# v2_guc_dag_t_m_savasan.net
KiCad netlist of a schematic drawn in EAGLE
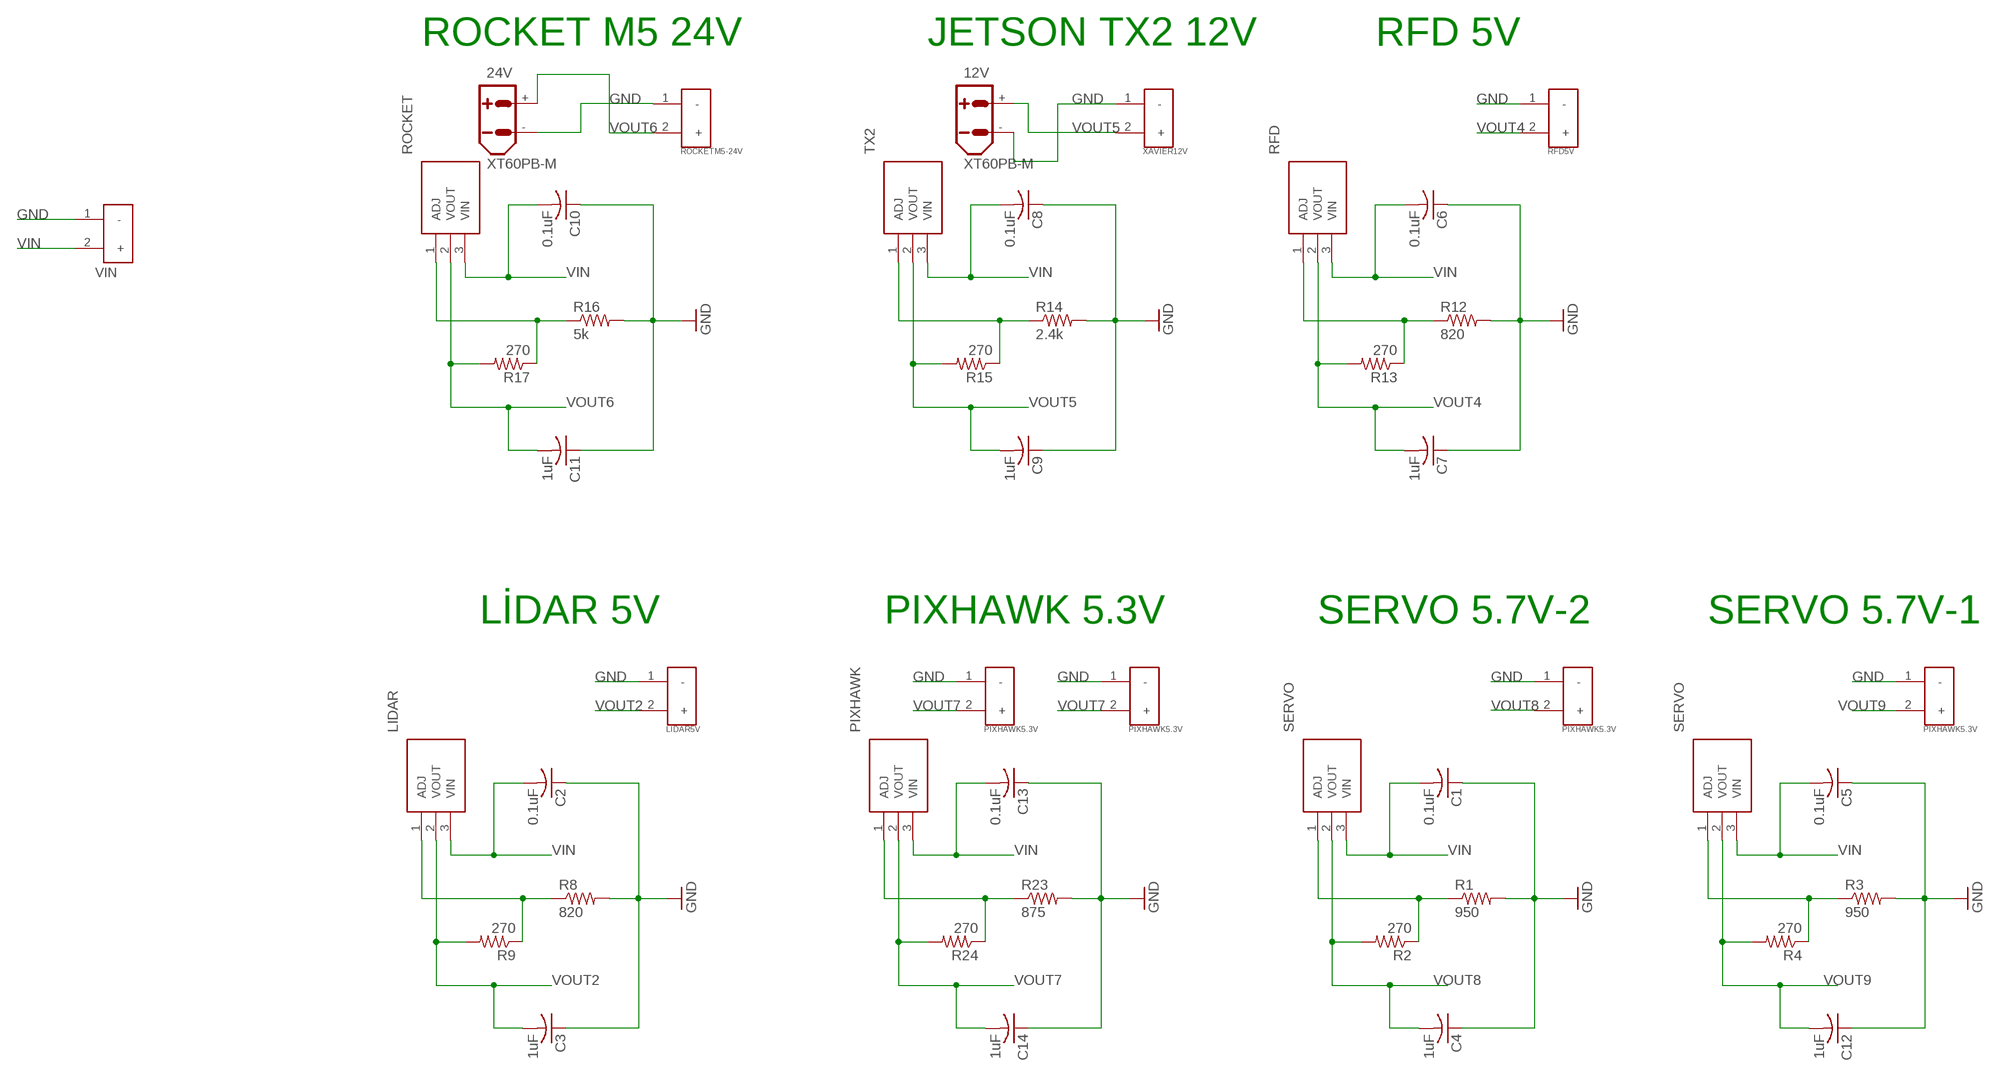
[diagram p0: schematic, sheet 1]

(export (version "E")
  (design (tool "Eeschema 10.0.6"))
  (components
    (comp (ref "12V")
      (value "XT60PB-M")
      (footprint "eagle-import:XT60PB-M")
      (libsource (lib "eagle-import") (part "XT60PB-M"))
    )
    (comp (ref "24V")
      (value "XT60PB-M")
      (footprint "eagle-import:XT60PB-M")
      (libsource (lib "eagle-import") (part "XT60PB-M"))
    )
    (comp (ref "C1")
      (value "0.1uF")
      (footprint "eagle-import:C0402K")
      (libsource (lib "eagle-import") (part "C-USC0402K"))
    )
    (comp (ref "C2")
      (value "0.1uF")
      (footprint "eagle-import:C0402K")
      (libsource (lib "eagle-import") (part "C-USC0402K"))
    )
    (comp (ref "C3")
      (value "1uF")
      (footprint "eagle-import:C0402K")
      (libsource (lib "eagle-import") (part "C-USC0402K"))
    )
    (comp (ref "C4")
      (value "1uF")
      (footprint "eagle-import:C0402K")
      (libsource (lib "eagle-import") (part "C-USC0402K"))
    )
    (comp (ref "C5")
      (value "0.1uF")
      (footprint "eagle-import:C0402K")
      (libsource (lib "eagle-import") (part "C-USC0402K"))
    )
    (comp (ref "C6")
      (value "0.1uF")
      (footprint "eagle-import:C0402K")
      (libsource (lib "eagle-import") (part "C-USC0402K"))
    )
    (comp (ref "C7")
      (value "1uF")
      (footprint "eagle-import:C0402K")
      (libsource (lib "eagle-import") (part "C-USC0402K"))
    )
    (comp (ref "C8")
      (value "0.1uF")
      (footprint "eagle-import:C0402K")
      (libsource (lib "eagle-import") (part "C-USC0402K"))
    )
    (comp (ref "C9")
      (value "1uF")
      (footprint "eagle-import:C0402K")
      (libsource (lib "eagle-import") (part "C-USC0402K"))
    )
    (comp (ref "C10")
      (value "0.1uF")
      (footprint "eagle-import:C0402K")
      (libsource (lib "eagle-import") (part "C-USC0402K"))
    )
    (comp (ref "C11")
      (value "1uF")
      (footprint "eagle-import:C0402K")
      (libsource (lib "eagle-import") (part "C-USC0402K"))
    )
    (comp (ref "C12")
      (value "1uF")
      (footprint "eagle-import:C0402K")
      (libsource (lib "eagle-import") (part "C-USC0402K"))
    )
    (comp (ref "C13")
      (value "0.1uF")
      (footprint "eagle-import:C0402K")
      (libsource (lib "eagle-import") (part "C-USC0402K"))
    )
    (comp (ref "C14")
      (value "1uF")
      (footprint "eagle-import:C0402K")
      (libsource (lib "eagle-import") (part "C-USC0402K"))
    )
    (comp (ref "IC5")
      (value "LIDAR")
      (footprint "eagle-import:TO254P470X1028X1955-3P")
      (fields
        (field (name "ARROW_PART_NUMBER") "LM338T/NOPB")
        (field (name "MOUSER_PART_NUMBER") "926-LM338T/NOPB")
      )
      (libsource (lib "eagle-import") (part "LM338T_NOPB"))
    )
    (comp (ref "IC7")
      (value "RFD")
      (footprint "eagle-import:TO254P470X1028X1955-3P")
      (fields
        (field (name "ARROW_PART_NUMBER") "LM338T/NOPB")
        (field (name "MOUSER_PART_NUMBER") "926-LM338T/NOPB")
      )
      (libsource (lib "eagle-import") (part "LM338T_NOPB"))
    )
    (comp (ref "IC8")
      (value "TX2")
      (footprint "eagle-import:TO254P470X1028X1955-3P")
      (fields
        (field (name "ARROW_PART_NUMBER") "LM338T/NOPB")
        (field (name "MOUSER_PART_NUMBER") "926-LM338T/NOPB")
      )
      (libsource (lib "eagle-import") (part "LM338T_NOPB"))
    )
    (comp (ref "IC9")
      (value "ROCKET")
      (footprint "eagle-import:TO254P470X1028X1955-3P")
      (fields
        (field (name "ARROW_PART_NUMBER") "LM338T/NOPB")
        (field (name "MOUSER_PART_NUMBER") "926-LM338T/NOPB")
      )
      (libsource (lib "eagle-import") (part "LM338T_NOPB"))
    )
    (comp (ref "IC13")
      (value "PIXHAWK")
      (footprint "eagle-import:TO254P470X1028X1955-3P")
      (fields
        (field (name "ARROW_PART_NUMBER") "LM338T/NOPB")
        (field (name "MOUSER_PART_NUMBER") "926-LM338T/NOPB")
      )
      (libsource (lib "eagle-import") (part "LM338T_NOPB"))
    )
    (comp (ref "J3")
      (value "VIN")
      (footprint "eagle-import:AMASS_XT60-M")
      (fields (field (name "MF") "AMASS") (field (name "MP") "XT60-M"))
      (libsource (lib "eagle-import") (part "XT60-M"))
    )
    (comp (ref "LIDAR5V")
      (value "LIDAR5V")
      (footprint "eagle-import:AMASS_XT60-M")
      (fields (field (name "MF") "AMASS") (field (name "MP") "XT60-M"))
      (libsource (lib "eagle-import") (part "XT60-M"))
    )
    (comp (ref "PIXHAWK5.3V-1")
      (value "PIXHAWK5.3V")
      (footprint "eagle-import:AMASS_XT60-M")
      (fields (field (name "MF") "AMASS") (field (name "MP") "XT60-M"))
      (libsource (lib "eagle-import") (part "XT60-M"))
    )
    (comp (ref "PIXHAWK5.3V-2")
      (value "PIXHAWK5.3V")
      (footprint "eagle-import:AMASS_XT60-M")
      (fields (field (name "MF") "AMASS") (field (name "MP") "XT60-M"))
      (libsource (lib "eagle-import") (part "XT60-M"))
    )
    (comp (ref "R1")
      (value "950")
      (footprint "eagle-import:R0805")
      (libsource (lib "eagle-import") (part "R-US_R0805"))
    )
    (comp (ref "R2")
      (value "270")
      (footprint "eagle-import:R0805")
      (libsource (lib "eagle-import") (part "R-US_R0805"))
    )
    (comp (ref "R3")
      (value "950")
      (footprint "eagle-import:R0805")
      (libsource (lib "eagle-import") (part "R-US_R0805"))
    )
    (comp (ref "R4")
      (value "270")
      (footprint "eagle-import:R0805")
      (libsource (lib "eagle-import") (part "R-US_R0805"))
    )
    (comp (ref "R8")
      (value "820")
      (footprint "eagle-import:R0805")
      (libsource (lib "eagle-import") (part "R-US_R0805"))
    )
    (comp (ref "R9")
      (value "270")
      (footprint "eagle-import:R0805")
      (libsource (lib "eagle-import") (part "R-US_R0805"))
    )
    (comp (ref "R12")
      (value "820")
      (footprint "eagle-import:R0805")
      (libsource (lib "eagle-import") (part "R-US_R0805"))
    )
    (comp (ref "R13")
      (value "270")
      (footprint "eagle-import:R0805")
      (libsource (lib "eagle-import") (part "R-US_R0805"))
    )
    (comp (ref "R14")
      (value "2.4k")
      (footprint "eagle-import:R0805")
      (libsource (lib "eagle-import") (part "R-US_R0805"))
    )
    (comp (ref "R15")
      (value "270")
      (footprint "eagle-import:R0805")
      (libsource (lib "eagle-import") (part "R-US_R0805"))
    )
    (comp (ref "R16")
      (value "5k")
      (footprint "eagle-import:R0805")
      (libsource (lib "eagle-import") (part "R-US_R0805"))
    )
    (comp (ref "R17")
      (value "270")
      (footprint "eagle-import:R0805")
      (libsource (lib "eagle-import") (part "R-US_R0805"))
    )
    (comp (ref "R23")
      (value "875")
      (footprint "eagle-import:R0805")
      (libsource (lib "eagle-import") (part "R-US_R0805"))
    )
    (comp (ref "R24")
      (value "270")
      (footprint "eagle-import:R0805")
      (libsource (lib "eagle-import") (part "R-US_R0805"))
    )
    (comp (ref "RFD5V")
      (value "RFD5V")
      (footprint "eagle-import:AMASS_XT60-M")
      (fields (field (name "MF") "AMASS") (field (name "MP") "XT60-M"))
      (libsource (lib "eagle-import") (part "XT60-M"))
    )
    (comp (ref "ROCKETM5-24V")
      (value "ROCKETM5-24V")
      (footprint "eagle-import:AMASS_XT60-M")
      (fields (field (name "MF") "AMASS") (field (name "MP") "XT60-M"))
      (libsource (lib "eagle-import") (part "XT60-M"))
    )
    (comp (ref "SERVO-1")
      (value "SERVO")
      (footprint "eagle-import:TO254P470X1028X1955-3P")
      (fields
        (field (name "ARROW_PART_NUMBER") "LM338T/NOPB")
        (field (name "MOUSER_PART_NUMBER") "926-LM338T/NOPB")
      )
      (libsource (lib "eagle-import") (part "LM338T_NOPB"))
    )
    (comp (ref "SERVO-2")
      (value "SERVO")
      (footprint "eagle-import:TO254P470X1028X1955-3P")
      (fields
        (field (name "ARROW_PART_NUMBER") "LM338T/NOPB")
        (field (name "MOUSER_PART_NUMBER") "926-LM338T/NOPB")
      )
      (libsource (lib "eagle-import") (part "LM338T_NOPB"))
    )
    (comp (ref "SERVO5.7V-1")
      (value "PIXHAWK5.3V")
      (footprint "eagle-import:AMASS_XT60-M")
      (fields (field (name "MF") "AMASS") (field (name "MP") "XT60-M"))
      (libsource (lib "eagle-import") (part "XT60-M"))
    )
    (comp (ref "SERVO5.7V-2")
      (value "PIXHAWK5.3V")
      (footprint "eagle-import:AMASS_XT60-M")
      (fields (field (name "MF") "AMASS") (field (name "MP") "XT60-M"))
      (libsource (lib "eagle-import") (part "XT60-M"))
    )
    (comp (ref "TX2-12V")
      (value "XAVIER12V")
      (footprint "eagle-import:AMASS_XT60-M")
      (fields (field (name "MF") "AMASS") (field (name "MP") "XT60-M"))
      (libsource (lib "eagle-import") (part "XT60-M"))
    )
  )
  (nets
    (net (code "1") (name "/VIN") (class "Default")
      (node (ref "C1") (pin "2") (pinfunction "2_2") (pintype "passive"))
      (node (ref "C10") (pin "2") (pinfunction "2_2") (pintype "passive"))
      (node (ref "C13") (pin "2") (pinfunction "2_2") (pintype "passive"))
      (node (ref "C2") (pin "2") (pinfunction "2_2") (pintype "passive"))
      (node (ref "C5") (pin "2") (pinfunction "2_2") (pintype "passive"))
      (node (ref "C6") (pin "2") (pinfunction "2_2") (pintype "passive"))
      (node (ref "C8") (pin "2") (pinfunction "2_2") (pintype "passive"))
      (node (ref "IC13") (pin "3") (pinfunction "VIN_3") (pintype "bidirectional"))
      (node (ref "IC5") (pin "3") (pinfunction "VIN_3") (pintype "bidirectional"))
      (node (ref "IC7") (pin "3") (pinfunction "VIN_3") (pintype "bidirectional"))
      (node (ref "IC8") (pin "3") (pinfunction "VIN_3") (pintype "bidirectional"))
      (node (ref "IC9") (pin "3") (pinfunction "VIN_3") (pintype "bidirectional"))
      (node (ref "J3") (pin "2") (pinfunction "+_2") (pintype "passive"))
      (node (ref "SERVO-1") (pin "3") (pinfunction "VIN_3") (pintype "bidirectional"))
      (node (ref "SERVO-2") (pin "3") (pinfunction "VIN_3") (pintype "bidirectional"))
    )
    (net (code "2") (name "/VOUT2") (class "Default")
      (node (ref "C3") (pin "2") (pinfunction "2_2") (pintype "passive"))
      (node (ref "IC5") (pin "2") (pinfunction "VOUT_2") (pintype "bidirectional"))
      (node (ref "LIDAR5V") (pin "2") (pinfunction "+_2") (pintype "passive"))
      (node (ref "R9") (pin "2") (pinfunction "2_2") (pintype "passive"))
    )
    (net (code "3") (name "/VOUT4") (class "Default")
      (node (ref "C7") (pin "2") (pinfunction "2_2") (pintype "passive"))
      (node (ref "IC7") (pin "2") (pinfunction "VOUT_2") (pintype "bidirectional"))
      (node (ref "R13") (pin "2") (pinfunction "2_2") (pintype "passive"))
      (node (ref "RFD5V") (pin "2") (pinfunction "+_2") (pintype "passive"))
    )
    (net (code "4") (name "/VOUT5") (class "Default")
      (node (ref "12V") (pin "+") (pinfunction "+_+") (pintype "power_in"))
      (node (ref "C9") (pin "2") (pinfunction "2_2") (pintype "passive"))
      (node (ref "IC8") (pin "2") (pinfunction "VOUT_2") (pintype "bidirectional"))
      (node (ref "R15") (pin "2") (pinfunction "2_2") (pintype "passive"))
      (node (ref "TX2-12V") (pin "2") (pinfunction "+_2") (pintype "passive"))
    )
    (net (code "5") (name "/VOUT6") (class "Default")
      (node (ref "24V") (pin "+") (pinfunction "+_+") (pintype "power_in"))
      (node (ref "C11") (pin "2") (pinfunction "2_2") (pintype "passive"))
      (node (ref "IC9") (pin "2") (pinfunction "VOUT_2") (pintype "bidirectional"))
      (node (ref "R17") (pin "2") (pinfunction "2_2") (pintype "passive"))
      (node (ref "ROCKETM5-24V") (pin "2") (pinfunction "+_2") (pintype "passive"))
    )
    (net (code "6") (name "/VOUT7") (class "Default")
      (node (ref "C14") (pin "2") (pinfunction "2_2") (pintype "passive"))
      (node (ref "IC13") (pin "2") (pinfunction "VOUT_2") (pintype "bidirectional"))
      (node (ref "PIXHAWK5.3V-1") (pin "2") (pinfunction "+_2") (pintype "passive"))
      (node (ref "PIXHAWK5.3V-2") (pin "2") (pinfunction "+_2") (pintype "passive"))
      (node (ref "R24") (pin "2") (pinfunction "2_2") (pintype "passive"))
    )
    (net (code "7") (name "/VOUT8") (class "Default")
      (node (ref "C4") (pin "2") (pinfunction "2_2") (pintype "passive"))
      (node (ref "R2") (pin "2") (pinfunction "2_2") (pintype "passive"))
      (node (ref "SERVO-2") (pin "2") (pinfunction "VOUT_2") (pintype "bidirectional"))
      (node (ref "SERVO5.7V-2") (pin "2") (pinfunction "+_2") (pintype "passive"))
    )
    (net (code "8") (name "/VOUT9") (class "Default")
      (node (ref "C12") (pin "2") (pinfunction "2_2") (pintype "passive"))
      (node (ref "R4") (pin "2") (pinfunction "2_2") (pintype "passive"))
      (node (ref "SERVO-1") (pin "2") (pinfunction "VOUT_2") (pintype "bidirectional"))
      (node (ref "SERVO5.7V-1") (pin "2") (pinfunction "+_2") (pintype "passive"))
    )
    (net (code "9") (name "GND") (class "Default")
      (node (ref "12V") (pin "-") (pinfunction "-_-") (pintype "power_in"))
      (node (ref "24V") (pin "-") (pinfunction "-_-") (pintype "power_in"))
      (node (ref "C1") (pin "1") (pinfunction "1_1") (pintype "passive"))
      (node (ref "C10") (pin "1") (pinfunction "1_1") (pintype "passive"))
      (node (ref "C11") (pin "1") (pinfunction "1_1") (pintype "passive"))
      (node (ref "C12") (pin "1") (pinfunction "1_1") (pintype "passive"))
      (node (ref "C13") (pin "1") (pinfunction "1_1") (pintype "passive"))
      (node (ref "C14") (pin "1") (pinfunction "1_1") (pintype "passive"))
      (node (ref "C2") (pin "1") (pinfunction "1_1") (pintype "passive"))
      (node (ref "C3") (pin "1") (pinfunction "1_1") (pintype "passive"))
      (node (ref "C4") (pin "1") (pinfunction "1_1") (pintype "passive"))
      (node (ref "C5") (pin "1") (pinfunction "1_1") (pintype "passive"))
      (node (ref "C6") (pin "1") (pinfunction "1_1") (pintype "passive"))
      (node (ref "C7") (pin "1") (pinfunction "1_1") (pintype "passive"))
      (node (ref "C8") (pin "1") (pinfunction "1_1") (pintype "passive"))
      (node (ref "C9") (pin "1") (pinfunction "1_1") (pintype "passive"))
      (node (ref "J3") (pin "1") (pinfunction "-_1") (pintype "passive"))
      (node (ref "LIDAR5V") (pin "1") (pinfunction "-_1") (pintype "passive"))
      (node (ref "PIXHAWK5.3V-1") (pin "1") (pinfunction "-_1") (pintype "passive"))
      (node (ref "PIXHAWK5.3V-2") (pin "1") (pinfunction "-_1") (pintype "passive"))
      (node (ref "R1") (pin "2") (pinfunction "2_2") (pintype "passive"))
      (node (ref "R12") (pin "2") (pinfunction "2_2") (pintype "passive"))
      (node (ref "R14") (pin "2") (pinfunction "2_2") (pintype "passive"))
      (node (ref "R16") (pin "2") (pinfunction "2_2") (pintype "passive"))
      (node (ref "R23") (pin "2") (pinfunction "2_2") (pintype "passive"))
      (node (ref "R3") (pin "2") (pinfunction "2_2") (pintype "passive"))
      (node (ref "R8") (pin "2") (pinfunction "2_2") (pintype "passive"))
      (node (ref "RFD5V") (pin "1") (pinfunction "-_1") (pintype "passive"))
      (node (ref "ROCKETM5-24V") (pin "1") (pinfunction "-_1") (pintype "passive"))
      (node (ref "SERVO5.7V-1") (pin "1") (pinfunction "-_1") (pintype "passive"))
      (node (ref "SERVO5.7V-2") (pin "1") (pinfunction "-_1") (pintype "passive"))
      (node (ref "TX2-12V") (pin "1") (pinfunction "-_1") (pintype "passive"))
    )
    (net (code "10") (name "Net-(IC5-ADJ)") (class "Default")
      (node (ref "IC5") (pin "1") (pinfunction "ADJ_1") (pintype "bidirectional"))
      (node (ref "R8") (pin "1") (pinfunction "1_1") (pintype "passive"))
      (node (ref "R9") (pin "1") (pinfunction "1_1") (pintype "passive"))
    )
    (net (code "11") (name "Net-(IC7-ADJ)") (class "Default")
      (node (ref "IC7") (pin "1") (pinfunction "ADJ_1") (pintype "bidirectional"))
      (node (ref "R12") (pin "1") (pinfunction "1_1") (pintype "passive"))
      (node (ref "R13") (pin "1") (pinfunction "1_1") (pintype "passive"))
    )
    (net (code "12") (name "Net-(IC8-ADJ)") (class "Default")
      (node (ref "IC8") (pin "1") (pinfunction "ADJ_1") (pintype "bidirectional"))
      (node (ref "R14") (pin "1") (pinfunction "1_1") (pintype "passive"))
      (node (ref "R15") (pin "1") (pinfunction "1_1") (pintype "passive"))
    )
    (net (code "13") (name "Net-(IC9-ADJ)") (class "Default")
      (node (ref "IC9") (pin "1") (pinfunction "ADJ_1") (pintype "bidirectional"))
      (node (ref "R16") (pin "1") (pinfunction "1_1") (pintype "passive"))
      (node (ref "R17") (pin "1") (pinfunction "1_1") (pintype "passive"))
    )
    (net (code "14") (name "Net-(IC13-ADJ)") (class "Default")
      (node (ref "IC13") (pin "1") (pinfunction "ADJ_1") (pintype "bidirectional"))
      (node (ref "R23") (pin "1") (pinfunction "1_1") (pintype "passive"))
      (node (ref "R24") (pin "1") (pinfunction "1_1") (pintype "passive"))
    )
    (net (code "15") (name "Net-(SERVO-1-ADJ)") (class "Default")
      (node (ref "R3") (pin "1") (pinfunction "1_1") (pintype "passive"))
      (node (ref "R4") (pin "1") (pinfunction "1_1") (pintype "passive"))
      (node (ref "SERVO-1") (pin "1") (pinfunction "ADJ_1") (pintype "bidirectional"))
    )
    (net (code "16") (name "Net-(SERVO-2-ADJ)") (class "Default")
      (node (ref "R1") (pin "1") (pinfunction "1_1") (pintype "passive"))
      (node (ref "R2") (pin "1") (pinfunction "1_1") (pintype "passive"))
      (node (ref "SERVO-2") (pin "1") (pinfunction "ADJ_1") (pintype "bidirectional"))
    )
  )
)
